# otto.net
KiCad netlist of a schematic drawn in EAGLE
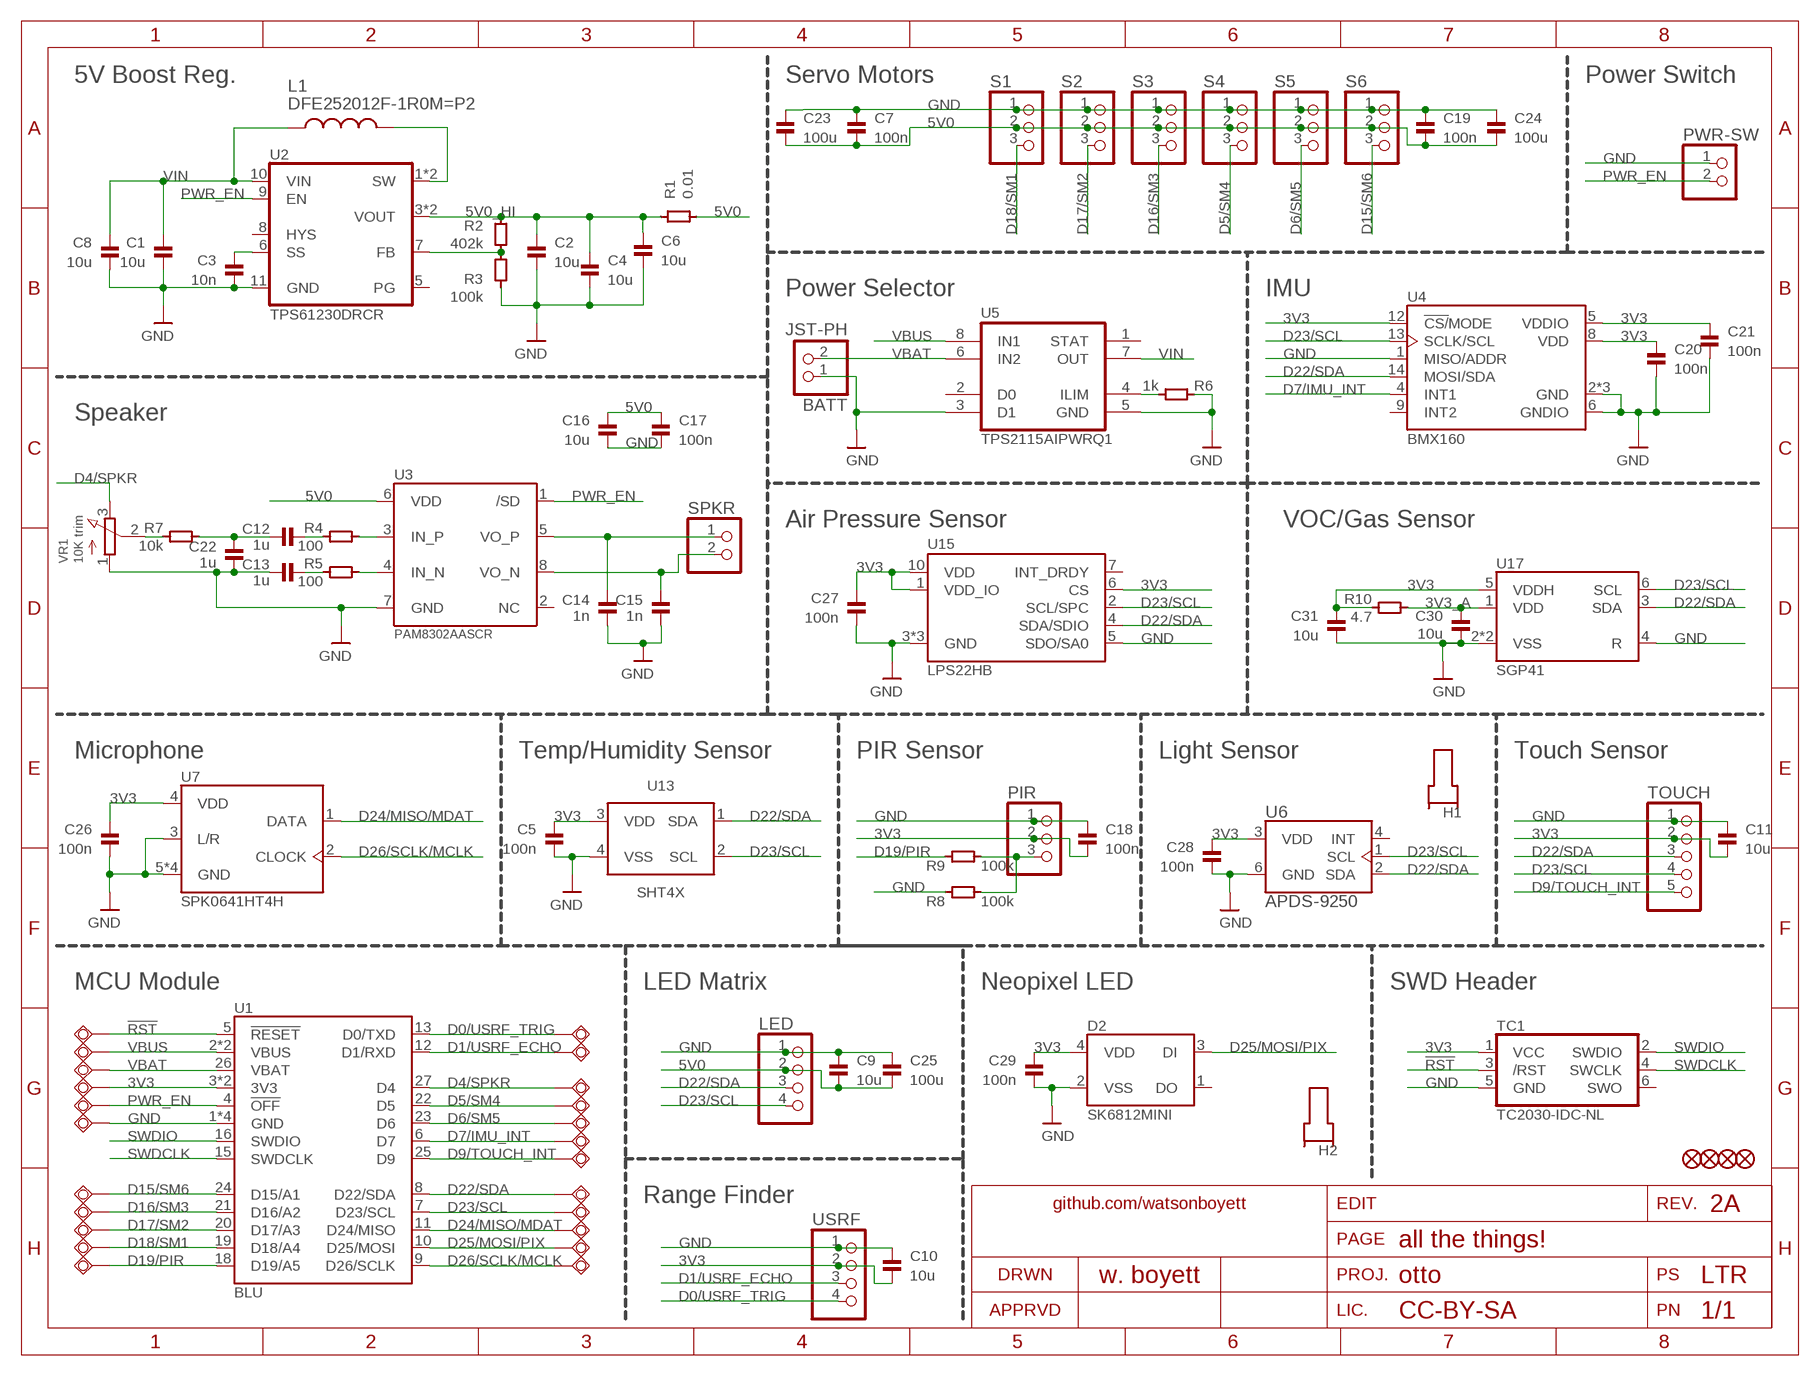
[diagram p0: schematic, sheet 1]

(export (version "E")
  (design (tool "Eeschema 10.0.6"))
  (components
    (comp (ref "3V3")
      (value "TPSQTP10R")
      (footprint "eagle-import:TP10R")
      (libsource (lib "eagle-import") (part "TPSQTP10R"))
    )
    (comp (ref "BATT")
      (value "JST-PH")
      (footprint "eagle-import:JSTPH2-S2B")
      (description "CONN HEADER SMD R/A 2POS 2MM")
      (fields
        (field (name "MFG") "JST")
        (field (name "MPN") "S2B-PH-SM4-TB(LF)(SN)")
        (field (name "PN-DGKY") "455-1749-1-ND")
      )
      (libsource (lib "eagle-import") (part "CON_JST_PH_2PIN-S2B"))
    )
    (comp (ref "C1")
      (value "10u")
      (footprint "eagle-import:_0603")
      (description "CAP CER 10UF 25V X5R 0805")
      (fields
        (field (name "MFG") "Samsung Electro-Mechanics")
        (field (name "MPN") "CL21A106KAYNNNE")
        (field (name "PN-DGKY") "445-11462-1-ND")
        (field (name "PN-DK") "1276-2891-1-ND")
      )
      (libsource (lib "eagle-import") (part "CAP_CERAMIC_0603"))
    )
    (comp (ref "C2")
      (value "10u")
      (footprint "eagle-import:_0603")
      (description "CAP CER 10UF 25V X5R 0805")
      (fields
        (field (name "MFG") "Samsung Electro-Mechanics")
        (field (name "MPN") "CL21A106KAYNNNE")
        (field (name "PN-DGKY") "445-11462-1-ND")
        (field (name "PN-DK") "1276-2891-1-ND")
      )
      (libsource (lib "eagle-import") (part "CAP_CERAMIC_0603"))
    )
    (comp (ref "C3")
      (value "10n")
      (footprint "eagle-import:_0603")
      (description "CAP CER 10UF 25V X5R 0805")
      (fields
        (field (name "MFG") "Samsung Electro-Mechanics")
        (field (name "MPN") "CL21A106KAYNNNE")
        (field (name "PN-DGKY") "445-11462-1-ND")
        (field (name "PN-DK") "1276-2891-1-ND")
      )
      (libsource (lib "eagle-import") (part "CAP_CERAMIC_0603"))
    )
    (comp (ref "C4")
      (value "10u")
      (footprint "eagle-import:_0603")
      (description "CAP CER 10UF 25V X5R 0805")
      (fields
        (field (name "MFG") "Samsung Electro-Mechanics")
        (field (name "MPN") "CL21A106KAYNNNE")
        (field (name "PN-DGKY") "445-11462-1-ND")
        (field (name "PN-DK") "1276-2891-1-ND")
      )
      (libsource (lib "eagle-import") (part "CAP_CERAMIC_0603"))
    )
    (comp (ref "C5")
      (value "100n")
      (footprint "eagle-import:_0603")
      (description "CAP CER 10UF 25V X5R 0805")
      (fields
        (field (name "MFG") "Samsung Electro-Mechanics")
        (field (name "MPN") "CL21A106KAYNNNE")
        (field (name "PN-DGKY") "445-11462-1-ND")
        (field (name "PN-DK") "1276-2891-1-ND")
      )
      (libsource (lib "eagle-import") (part "CAP_CERAMIC_0603"))
    )
    (comp (ref "C6")
      (value "10u")
      (footprint "eagle-import:_0603")
      (description "CAP CER 10UF 25V X5R 0805")
      (fields
        (field (name "MFG") "Samsung Electro-Mechanics")
        (field (name "MPN") "CL21A106KAYNNNE")
        (field (name "PN-DGKY") "445-11462-1-ND")
        (field (name "PN-DK") "1276-2891-1-ND")
      )
      (libsource (lib "eagle-import") (part "CAP_CERAMIC_0603"))
    )
    (comp (ref "C7")
      (value "100n")
      (footprint "eagle-import:_0603")
      (description "CAP CER 10UF 25V X5R 0805")
      (fields
        (field (name "MFG") "Samsung Electro-Mechanics")
        (field (name "MPN") "CL21A106KAYNNNE")
        (field (name "PN-DGKY") "445-11462-1-ND")
        (field (name "PN-DK") "1276-2891-1-ND")
      )
      (libsource (lib "eagle-import") (part "CAP_CERAMIC_0603"))
    )
    (comp (ref "C8")
      (value "10u")
      (footprint "eagle-import:_0603")
      (description "CAP CER 10UF 25V X5R 0805")
      (fields
        (field (name "MFG") "Samsung Electro-Mechanics")
        (field (name "MPN") "CL21A106KAYNNNE")
        (field (name "PN-DGKY") "445-11462-1-ND")
        (field (name "PN-DK") "1276-2891-1-ND")
      )
      (libsource (lib "eagle-import") (part "CAP_CERAMIC_0603"))
    )
    (comp (ref "C9")
      (value "10u")
      (footprint "eagle-import:_0603")
      (description "CAP CER 10UF 25V X5R 0805")
      (fields
        (field (name "MFG") "Samsung Electro-Mechanics")
        (field (name "MPN") "CL21A106KAYNNNE")
        (field (name "PN-DGKY") "445-11462-1-ND")
        (field (name "PN-DK") "1276-2891-1-ND")
      )
      (libsource (lib "eagle-import") (part "CAP_CERAMIC_0603"))
    )
    (comp (ref "C10")
      (value "10u")
      (footprint "eagle-import:_0603")
      (description "CAP CER 10UF 25V X5R 0805")
      (fields
        (field (name "MFG") "Samsung Electro-Mechanics")
        (field (name "MPN") "CL21A106KAYNNNE")
        (field (name "PN-DGKY") "445-11462-1-ND")
        (field (name "PN-DK") "1276-2891-1-ND")
      )
      (libsource (lib "eagle-import") (part "CAP_CERAMIC_0603"))
    )
    (comp (ref "C11")
      (value "10u")
      (footprint "eagle-import:_0603")
      (description "CAP CER 10UF 25V X5R 0805")
      (fields
        (field (name "MFG") "Samsung Electro-Mechanics")
        (field (name "MPN") "CL21A106KAYNNNE")
        (field (name "PN-DGKY") "445-11462-1-ND")
        (field (name "PN-DK") "1276-2891-1-ND")
      )
      (libsource (lib "eagle-import") (part "CAP_CERAMIC_0603"))
    )
    (comp (ref "C12")
      (value "1u")
      (footprint "eagle-import:_0603")
      (description "CAP CER 10UF 25V X5R 0805")
      (fields
        (field (name "MFG") "Samsung Electro-Mechanics")
        (field (name "MPN") "CL21A106KAYNNNE")
        (field (name "PN-DGKY") "445-11462-1-ND")
        (field (name "PN-DK") "1276-2891-1-ND")
      )
      (libsource (lib "eagle-import") (part "CAP_CERAMIC_0603"))
    )
    (comp (ref "C13")
      (value "1u")
      (footprint "eagle-import:_0603")
      (description "CAP CER 10UF 25V X5R 0805")
      (fields
        (field (name "MFG") "Samsung Electro-Mechanics")
        (field (name "MPN") "CL21A106KAYNNNE")
        (field (name "PN-DGKY") "445-11462-1-ND")
        (field (name "PN-DK") "1276-2891-1-ND")
      )
      (libsource (lib "eagle-import") (part "CAP_CERAMIC_0603"))
    )
    (comp (ref "C14")
      (value "1n")
      (footprint "eagle-import:_0603")
      (description "CAP CER 10UF 25V X5R 0805")
      (fields
        (field (name "MFG") "Samsung Electro-Mechanics")
        (field (name "MPN") "CL21A106KAYNNNE")
        (field (name "PN-DGKY") "445-11462-1-ND")
        (field (name "PN-DK") "1276-2891-1-ND")
      )
      (libsource (lib "eagle-import") (part "CAP_CERAMIC_0603"))
    )
    (comp (ref "C15")
      (value "1n")
      (footprint "eagle-import:_0603")
      (description "CAP CER 10UF 25V X5R 0805")
      (fields
        (field (name "MFG") "Samsung Electro-Mechanics")
        (field (name "MPN") "CL21A106KAYNNNE")
        (field (name "PN-DGKY") "445-11462-1-ND")
        (field (name "PN-DK") "1276-2891-1-ND")
      )
      (libsource (lib "eagle-import") (part "CAP_CERAMIC_0603"))
    )
    (comp (ref "C16")
      (value "10u")
      (footprint "eagle-import:_0603")
      (description "CAP CER 10UF 25V X5R 0805")
      (fields
        (field (name "MFG") "Samsung Electro-Mechanics")
        (field (name "MPN") "CL21A106KAYNNNE")
        (field (name "PN-DGKY") "445-11462-1-ND")
        (field (name "PN-DK") "1276-2891-1-ND")
      )
      (libsource (lib "eagle-import") (part "CAP_CERAMIC_0603"))
    )
    (comp (ref "C17")
      (value "100n")
      (footprint "eagle-import:_0603")
      (description "CAP CER 10UF 25V X5R 0805")
      (fields
        (field (name "MFG") "Samsung Electro-Mechanics")
        (field (name "MPN") "CL21A106KAYNNNE")
        (field (name "PN-DGKY") "445-11462-1-ND")
        (field (name "PN-DK") "1276-2891-1-ND")
      )
      (libsource (lib "eagle-import") (part "CAP_CERAMIC_0603"))
    )
    (comp (ref "C18")
      (value "100n")
      (footprint "eagle-import:_0603")
      (description "CAP CER 10UF 25V X5R 0805")
      (fields
        (field (name "MFG") "Samsung Electro-Mechanics")
        (field (name "MPN") "CL21A106KAYNNNE")
        (field (name "PN-DGKY") "445-11462-1-ND")
        (field (name "PN-DK") "1276-2891-1-ND")
      )
      (libsource (lib "eagle-import") (part "CAP_CERAMIC_0603"))
    )
    (comp (ref "C19")
      (value "100n")
      (footprint "eagle-import:_0603")
      (description "CAP CER 10UF 25V X5R 0805")
      (fields
        (field (name "MFG") "Samsung Electro-Mechanics")
        (field (name "MPN") "CL21A106KAYNNNE")
        (field (name "PN-DGKY") "445-11462-1-ND")
        (field (name "PN-DK") "1276-2891-1-ND")
      )
      (libsource (lib "eagle-import") (part "CAP_CERAMIC_0603"))
    )
    (comp (ref "C20")
      (value "100n")
      (footprint "eagle-import:_0603")
      (description "CAP CER 10UF 25V X5R 0805")
      (fields
        (field (name "MFG") "Samsung Electro-Mechanics")
        (field (name "MPN") "CL21A106KAYNNNE")
        (field (name "PN-DGKY") "445-11462-1-ND")
        (field (name "PN-DK") "1276-2891-1-ND")
      )
      (libsource (lib "eagle-import") (part "CAP_CERAMIC_0603"))
    )
    (comp (ref "C21")
      (value "100n")
      (footprint "eagle-import:_0603")
      (description "CAP CER 10UF 25V X5R 0805")
      (fields
        (field (name "MFG") "Samsung Electro-Mechanics")
        (field (name "MPN") "CL21A106KAYNNNE")
        (field (name "PN-DGKY") "445-11462-1-ND")
        (field (name "PN-DK") "1276-2891-1-ND")
      )
      (libsource (lib "eagle-import") (part "CAP_CERAMIC_0603"))
    )
    (comp (ref "C22")
      (value "1u")
      (footprint "eagle-import:_0603")
      (description "CAP CER 10UF 25V X5R 0805")
      (fields
        (field (name "MFG") "Samsung Electro-Mechanics")
        (field (name "MPN") "CL21A106KAYNNNE")
        (field (name "PN-DGKY") "445-11462-1-ND")
        (field (name "PN-DK") "1276-2891-1-ND")
      )
      (libsource (lib "eagle-import") (part "CAP_CERAMIC_0603"))
    )
    (comp (ref "C23")
      (value "100u")
      (footprint "eagle-import:_1206")
      (description "CAP CER 10UF 25V X5R 0805")
      (fields
        (field (name "MFG") "Samsung Electro-Mechanics")
        (field (name "MPN") "CL21A106KAYNNNE")
        (field (name "PN-DGKY") "445-11462-1-ND")
        (field (name "PN-DK") "1276-2891-1-ND")
      )
      (libsource (lib "eagle-import") (part "CAP_CERAMIC_1206"))
    )
    (comp (ref "C24")
      (value "100u")
      (footprint "eagle-import:_1206")
      (description "CAP CER 10UF 25V X5R 0805")
      (fields
        (field (name "MFG") "Samsung Electro-Mechanics")
        (field (name "MPN") "CL21A106KAYNNNE")
        (field (name "PN-DGKY") "445-11462-1-ND")
        (field (name "PN-DK") "1276-2891-1-ND")
      )
      (libsource (lib "eagle-import") (part "CAP_CERAMIC_1206"))
    )
    (comp (ref "C25")
      (value "100u")
      (footprint "eagle-import:_1206")
      (description "CAP CER 10UF 25V X5R 0805")
      (fields
        (field (name "MFG") "Samsung Electro-Mechanics")
        (field (name "MPN") "CL21A106KAYNNNE")
        (field (name "PN-DGKY") "445-11462-1-ND")
        (field (name "PN-DK") "1276-2891-1-ND")
      )
      (libsource (lib "eagle-import") (part "CAP_CERAMIC_1206"))
    )
    (comp (ref "C26")
      (value "100n")
      (footprint "eagle-import:_0603")
      (description "CAP CER 10UF 25V X5R 0805")
      (fields
        (field (name "MFG") "Samsung Electro-Mechanics")
        (field (name "MPN") "CL21A106KAYNNNE")
        (field (name "PN-DGKY") "445-11462-1-ND")
        (field (name "PN-DK") "1276-2891-1-ND")
      )
      (libsource (lib "eagle-import") (part "CAP_CERAMIC_0603"))
    )
    (comp (ref "C27")
      (value "100n")
      (footprint "eagle-import:_0603")
      (description "CAP CER 10UF 25V X5R 0805")
      (fields
        (field (name "MFG") "Samsung Electro-Mechanics")
        (field (name "MPN") "CL21A106KAYNNNE")
        (field (name "PN-DGKY") "445-11462-1-ND")
        (field (name "PN-DK") "1276-2891-1-ND")
      )
      (libsource (lib "eagle-import") (part "CAP_CERAMIC_0603"))
    )
    (comp (ref "C28")
      (value "100n")
      (footprint "eagle-import:_0603")
      (description "CAP CER 10UF 25V X5R 0805")
      (fields
        (field (name "MFG") "Samsung Electro-Mechanics")
        (field (name "MPN") "CL21A106KAYNNNE")
        (field (name "PN-DGKY") "445-11462-1-ND")
        (field (name "PN-DK") "1276-2891-1-ND")
      )
      (libsource (lib "eagle-import") (part "CAP_CERAMIC_0603"))
    )
    (comp (ref "C29")
      (value "100n")
      (footprint "eagle-import:_0603")
      (description "CAP CER 10UF 25V X5R 0805")
      (fields
        (field (name "MFG") "Samsung Electro-Mechanics")
        (field (name "MPN") "CL21A106KAYNNNE")
        (field (name "PN-DGKY") "445-11462-1-ND")
        (field (name "PN-DK") "1276-2891-1-ND")
      )
      (libsource (lib "eagle-import") (part "CAP_CERAMIC_0603"))
    )
    (comp (ref "C30")
      (value "10u")
      (footprint "eagle-import:_0603")
      (description "CAP CER 10UF 25V X5R 0805")
      (fields
        (field (name "MFG") "Samsung Electro-Mechanics")
        (field (name "MPN") "CL21A106KAYNNNE")
        (field (name "PN-DGKY") "445-11462-1-ND")
        (field (name "PN-DK") "1276-2891-1-ND")
      )
      (libsource (lib "eagle-import") (part "CAP_CERAMIC_0603"))
    )
    (comp (ref "C31")
      (value "10u")
      (footprint "eagle-import:_0603")
      (description "CAP CER 10UF 25V X5R 0805")
      (fields
        (field (name "MFG") "Samsung Electro-Mechanics")
        (field (name "MPN") "CL21A106KAYNNNE")
        (field (name "PN-DGKY") "445-11462-1-ND")
        (field (name "PN-DK") "1276-2891-1-ND")
      )
      (libsource (lib "eagle-import") (part "CAP_CERAMIC_0603"))
    )
    (comp (ref "D0")
      (value "TPSQTP10R")
      (footprint "eagle-import:TP10R")
      (libsource (lib "eagle-import") (part "TPSQTP10R"))
    )
    (comp (ref "D1")
      (value "TPSQTP10R")
      (footprint "eagle-import:TP10R")
      (libsource (lib "eagle-import") (part "TPSQTP10R"))
    )
    (comp (ref "D2")
      (value "SK6812MINI")
      (footprint "eagle-import:SK6812MINI")
      (fields
        (field (name "DIGI-KEY_PART_NUMBER") "1528-1542-ND")
        (field (name "MF") "Adafruit Industries")
        (field (name "MP") "2659")
      )
      (libsource (lib "eagle-import") (part "SK6812MINI"))
    )
    (comp (ref "D4")
      (value "TPSQTP10R")
      (footprint "eagle-import:TP10R")
      (libsource (lib "eagle-import") (part "TPSQTP10R"))
    )
    (comp (ref "D5")
      (value "TPSQTP10R")
      (footprint "eagle-import:TP10R")
      (libsource (lib "eagle-import") (part "TPSQTP10R"))
    )
    (comp (ref "D6")
      (value "TPSQTP10R")
      (footprint "eagle-import:TP10R")
      (libsource (lib "eagle-import") (part "TPSQTP10R"))
    )
    (comp (ref "D7")
      (value "TPSQTP10R")
      (footprint "eagle-import:TP10R")
      (libsource (lib "eagle-import") (part "TPSQTP10R"))
    )
    (comp (ref "D9")
      (value "TPSQTP10R")
      (footprint "eagle-import:TP10R")
      (libsource (lib "eagle-import") (part "TPSQTP10R"))
    )
    (comp (ref "D15")
      (value "TPSQTP10R")
      (footprint "eagle-import:TP10R")
      (libsource (lib "eagle-import") (part "TPSQTP10R"))
    )
    (comp (ref "D16")
      (value "TPSQTP10R")
      (footprint "eagle-import:TP10R")
      (libsource (lib "eagle-import") (part "TPSQTP10R"))
    )
    (comp (ref "D17")
      (value "TPSQTP10R")
      (footprint "eagle-import:TP10R")
      (libsource (lib "eagle-import") (part "TPSQTP10R"))
    )
    (comp (ref "D18")
      (value "TPSQTP10R")
      (footprint "eagle-import:TP10R")
      (libsource (lib "eagle-import") (part "TPSQTP10R"))
    )
    (comp (ref "D19")
      (value "TPSQTP10R")
      (footprint "eagle-import:TP10R")
      (libsource (lib "eagle-import") (part "TPSQTP10R"))
    )
    (comp (ref "D24")
      (value "TPSQTP10R")
      (footprint "eagle-import:TP10R")
      (libsource (lib "eagle-import") (part "TPSQTP10R"))
    )
    (comp (ref "D25")
      (value "TPSQTP10R")
      (footprint "eagle-import:TP10R")
      (libsource (lib "eagle-import") (part "TPSQTP10R"))
    )
    (comp (ref "D26")
      (value "TPSQTP10R")
      (footprint "eagle-import:TP10R")
      (libsource (lib "eagle-import") (part "TPSQTP10R"))
    )
    (comp (ref "FID1")
      (value "FIDUCIAL0.8MM")
      (footprint "eagle-import:FIDUCIAL_0.8MM")
      (libsource (lib "eagle-import") (part "FIDUCIAL0.8MM"))
    )
    (comp (ref "FID2")
      (value "FIDUCIAL0.8MM")
      (footprint "eagle-import:FIDUCIAL_0.8MM")
      (libsource (lib "eagle-import") (part "FIDUCIAL0.8MM"))
    )
    (comp (ref "FID3")
      (value "FIDUCIAL0.8MM")
      (footprint "eagle-import:FIDUCIAL_0.8MM")
      (libsource (lib "eagle-import") (part "FIDUCIAL0.8MM"))
    )
    (comp (ref "FID5")
      (value "FIDUCIAL0.8MM")
      (footprint "eagle-import:FIDUCIAL_0.8MM")
      (libsource (lib "eagle-import") (part "FIDUCIAL0.8MM"))
    )
    (comp (ref "GND")
      (value "TPSQTP10R")
      (footprint "eagle-import:TP10R")
      (libsource (lib "eagle-import") (part "TPSQTP10R"))
    )
    (comp (ref "H1")
      (value "VLP-XXX-X")
      (footprint "eagle-import:VLP-XXX-X")
      (libsource (lib "eagle-import") (part "VLP-XXX-X"))
    )
    (comp (ref "H2")
      (value "VLP-XXX-X")
      (footprint "eagle-import:VLP-XXX-X")
      (libsource (lib "eagle-import") (part "VLP-XXX-X"))
    )
    (comp (ref "L1")
      (value "DFE252012F-1R0M=P2")
      (footprint "eagle-import:INDC2520X120N")
      (fields (field (name "DIGI-KEY_PART_NUMBER") "490-13053-1-ND") (field (name "MF") "Murata Electronics"))
      (libsource (lib "eagle-import") (part "DFE252012F-1R0M=P2"))
    )
    (comp (ref "LED")
      (value "PINHD-1X4")
      (footprint "eagle-import:1X04")
      (libsource (lib "eagle-import") (part "PINHD-1X4"))
    )
    (comp (ref "PEN")
      (value "TPSQTP10R")
      (footprint "eagle-import:TP10R")
      (libsource (lib "eagle-import") (part "TPSQTP10R"))
    )
    (comp (ref "PIR")
      (value "PINHD-1X3")
      (footprint "eagle-import:1X03")
      (libsource (lib "eagle-import") (part "PINHD-1X3"))
    )
    (comp (ref "PWR-SW")
      (value "PINHD-1X2")
      (footprint "eagle-import:1X02")
      (libsource (lib "eagle-import") (part "PINHD-1X2"))
    )
    (comp (ref "R1")
      (value "0.01")
      (footprint "eagle-import:_0603")
      (libsource (lib "eagle-import") (part "RESISTOR_0603"))
    )
    (comp (ref "R2")
      (value "402k")
      (footprint "eagle-import:_0603")
      (libsource (lib "eagle-import") (part "RESISTOR_0603"))
    )
    (comp (ref "R3")
      (value "100k")
      (footprint "eagle-import:_0603")
      (libsource (lib "eagle-import") (part "RESISTOR_0603"))
    )
    (comp (ref "R4")
      (value "100")
      (footprint "eagle-import:_0603")
      (libsource (lib "eagle-import") (part "RESISTOR_0603"))
    )
    (comp (ref "R5")
      (value "100")
      (footprint "eagle-import:_0603")
      (libsource (lib "eagle-import") (part "RESISTOR_0603"))
    )
    (comp (ref "R6")
      (value "1k")
      (footprint "eagle-import:_0603")
      (libsource (lib "eagle-import") (part "RESISTOR_0603"))
    )
    (comp (ref "R7")
      (value "10k")
      (footprint "eagle-import:_0603")
      (libsource (lib "eagle-import") (part "RESISTOR_0603"))
    )
    (comp (ref "R8")
      (value "100k")
      (footprint "eagle-import:_0603")
      (libsource (lib "eagle-import") (part "RESISTOR_0603"))
    )
    (comp (ref "R9")
      (value "100k")
      (footprint "eagle-import:_0603")
      (libsource (lib "eagle-import") (part "RESISTOR_0603"))
    )
    (comp (ref "R10")
      (value "4.7")
      (footprint "eagle-import:_0603")
      (libsource (lib "eagle-import") (part "RESISTOR_0603"))
    )
    (comp (ref "RST")
      (value "TPSQTP10R")
      (footprint "eagle-import:TP10R")
      (libsource (lib "eagle-import") (part "TPSQTP10R"))
    )
    (comp (ref "S1")
      (value "PINHD-1X3")
      (footprint "eagle-import:1X03")
      (libsource (lib "eagle-import") (part "PINHD-1X3"))
    )
    (comp (ref "S2")
      (value "PINHD-1X3")
      (footprint "eagle-import:1X03")
      (libsource (lib "eagle-import") (part "PINHD-1X3"))
    )
    (comp (ref "S3")
      (value "PINHD-1X3")
      (footprint "eagle-import:1X03")
      (libsource (lib "eagle-import") (part "PINHD-1X3"))
    )
    (comp (ref "S4")
      (value "PINHD-1X3")
      (footprint "eagle-import:1X03")
      (libsource (lib "eagle-import") (part "PINHD-1X3"))
    )
    (comp (ref "S5")
      (value "PINHD-1X3")
      (footprint "eagle-import:1X03")
      (libsource (lib "eagle-import") (part "PINHD-1X3"))
    )
    (comp (ref "S6")
      (value "PINHD-1X3")
      (footprint "eagle-import:1X03")
      (libsource (lib "eagle-import") (part "PINHD-1X3"))
    )
    (comp (ref "SCL")
      (value "TPSQTP10R")
      (footprint "eagle-import:TP10R")
      (libsource (lib "eagle-import") (part "TPSQTP10R"))
    )
    (comp (ref "SDA")
      (value "TPSQTP10R")
      (footprint "eagle-import:TP10R")
      (libsource (lib "eagle-import") (part "TPSQTP10R"))
    )
    (comp (ref "SPKR")
      (value "PINHD-1X2")
      (footprint "eagle-import:1X02")
      (libsource (lib "eagle-import") (part "PINHD-1X2"))
    )
    (comp (ref "TC1")
      (value "TC2030-IDC-NL")
      (footprint "eagle-import:TC2030-NL")
      (fields (field (name "MFG") "Tag-Connect") (field (name "MPN") "TC2030-IDC"))
      (libsource (lib "eagle-import") (part "TC2030-IDC-NL"))
    )
    (comp (ref "TOUCH")
      (value "PINHD-1X5")
      (footprint "eagle-import:1X05")
      (libsource (lib "eagle-import") (part "PINHD-1X5"))
    )
    (comp (ref "U1")
      (value "BLU")
      (footprint "eagle-import:BLU")
      (libsource (lib "eagle-import") (part "BLU"))
    )
    (comp (ref "U2")
      (value "TPS61230DRCR")
      (footprint "eagle-import:VREG_V62_16624-01YE")
      (fields (field (name "DIGI-KEY_PART_NUMBER") "296-37761-1-ND") (field (name "MF") "Texas Instruments"))
      (libsource (lib "eagle-import") (part "TPS61230DRCR"))
    )
    (comp (ref "U3")
      (value "PAM8302AASCR")
      (footprint "eagle-import:MSOP8_0.65MM")
      (libsource (lib "eagle-import") (part "AUDIOAMP_PAM8302A"))
    )
    (comp (ref "U4")
      (value "BMX160")
      (footprint "eagle-import:PQFN50P250X300X100-14N")
      (fields (field (name "MF") "Bosch Sensortec"))
      (libsource (lib "eagle-import") (part "BMX160"))
    )
    (comp (ref "U5")
      (value "TPS2115AIPWRQ1")
      (footprint "eagle-import:SOP65P640X120-8N")
      (fields (field (name "MF") "Texas Instruments"))
      (libsource (lib "eagle-import") (part "TPS2115AIPWRQ1"))
    )
    (comp (ref "U6")
      (value "APDS-9250")
      (footprint "eagle-import:SON65P200X200X75-6N")
      (fields (field (name "DIGI-KEY_PART_NUMBER") "516-3293-1-ND") (field (name "MF") "Broadcom Limited"))
      (libsource (lib "eagle-import") (part "APDS-9250"))
    )
    (comp (ref "U7")
      (value "SPK0641HT4H")
      (footprint "eagle-import:SPK0641HT4H-1")
      (fields (field (name "MFG") "Knowles") (field (name "MPN") "SPK0641HT4H-1"))
      (libsource (lib "eagle-import") (part "SPK0641HT4H"))
    )
    (comp (ref "U13")
      (value "SHT4X")
      (footprint "eagle-import:SHT4X-DFN4")
      (fields (field (name "MFG") "Sensirion AG") (field (name "MPN") "SHT21"))
      (libsource (lib "eagle-import") (part "SHT4X"))
    )
    (comp (ref "U15")
      (value "LPS22HB")
      (footprint "eagle-import:HLGA-10L")
      (fields (field (name "MFG") "STMicroelectronics") (field (name "MPN") "LPS22HBTR"))
      (libsource (lib "eagle-import") (part "LPS22HB"))
    )
    (comp (ref "U17")
      (value "SGP41")
      (footprint "eagle-import:SGP41")
      (libsource (lib "eagle-import") (part "SGP41"))
    )
    (comp (ref "USRF")
      (value "PINHD-1X4")
      (footprint "eagle-import:1X04")
      (libsource (lib "eagle-import") (part "PINHD-1X4"))
    )
    (comp (ref "VBS")
      (value "TPSQTP10R")
      (footprint "eagle-import:TP10R")
      (libsource (lib "eagle-import") (part "TPSQTP10R"))
    )
    (comp (ref "VBT")
      (value "TPSQTP10R")
      (footprint "eagle-import:TP10R")
      (libsource (lib "eagle-import") (part "TPSQTP10R"))
    )
    (comp (ref "VR1")
      (value "10K trim")
      (footprint "eagle-import:TRIMPOT_BOURNS_3303W")
      (libsource (lib "eagle-import") (part "TRIMPOT3303W/X"))
    )
  )
  (nets
    (net (code "1") (name "/3V3") (class "Default")
      (node (ref "3V3") (pin "TP") (pinfunction "TP_TP") (pintype "input"))
      (node (ref "C10") (pin "2") (pinfunction "2_2") (pintype "passive"))
      (node (ref "C11") (pin "2") (pinfunction "2_2") (pintype "passive"))
      (node (ref "C18") (pin "2") (pinfunction "2_2") (pintype "passive"))
      (node (ref "C20") (pin "1") (pinfunction "1_1") (pintype "passive"))
      (node (ref "C21") (pin "1") (pinfunction "1_1") (pintype "passive"))
      (node (ref "C26") (pin "1") (pinfunction "1_1") (pintype "passive"))
      (node (ref "C27") (pin "1") (pinfunction "1_1") (pintype "passive"))
      (node (ref "C28") (pin "1") (pinfunction "1_1") (pintype "passive"))
      (node (ref "C29") (pin "1") (pinfunction "1_1") (pintype "passive"))
      (node (ref "C31") (pin "1") (pinfunction "1_1") (pintype "passive"))
      (node (ref "C5") (pin "1") (pinfunction "1_1") (pintype "passive"))
      (node (ref "D2") (pin "4") (pinfunction "VDD_4") (pintype "power_in"))
      (node (ref "PIR") (pin "2") (pinfunction "2_2") (pintype "passive"))
      (node (ref "R10") (pin "1") (pinfunction "1_1") (pintype "passive"))
      (node (ref "TC1") (pin "1") (pinfunction "VCC_1") (pintype "passive"))
      (node (ref "TOUCH") (pin "2") (pinfunction "2_2") (pintype "passive"))
      (node (ref "U1") (pin "28") (pinfunction "3V3_28") (pintype "bidirectional"))
      (node (ref "U1") (pin "3") (pinfunction "3V3_3") (pintype "bidirectional"))
      (node (ref "U13") (pin "3") (pinfunction "VDD_3") (pintype "bidirectional"))
      (node (ref "U15") (pin "1") (pinfunction "VDD_IO_1") (pintype "bidirectional"))
      (node (ref "U15") (pin "10") (pinfunction "VDD_10") (pintype "bidirectional"))
      (node (ref "U15") (pin "6") (pinfunction "CS_6") (pintype "bidirectional"))
      (node (ref "U17") (pin "5") (pinfunction "VDDH_5") (pintype "bidirectional"))
      (node (ref "U4") (pin "12") (pinfunction "~{CS/}MODE_12") (pintype "input"))
      (node (ref "U4") (pin "5") (pinfunction "VDDIO_5") (pintype "power_in"))
      (node (ref "U4") (pin "8") (pinfunction "VDD_8") (pintype "power_in"))
      (node (ref "U6") (pin "3") (pinfunction "VDD_3") (pintype "power_in"))
      (node (ref "U7") (pin "4") (pinfunction "VDD_4") (pintype "power_in"))
      (node (ref "USRF") (pin "2") (pinfunction "2_2") (pintype "passive"))
    )
    (net (code "2") (name "/3V3_A") (class "Default")
      (node (ref "C30") (pin "1") (pinfunction "1_1") (pintype "passive"))
      (node (ref "R10") (pin "2") (pinfunction "2_2") (pintype "passive"))
      (node (ref "U17") (pin "1") (pinfunction "VDD_1") (pintype "bidirectional"))
    )
    (net (code "3") (name "/5V0") (class "Default")
      (node (ref "C16") (pin "1") (pinfunction "1_1") (pintype "passive"))
      (node (ref "C17") (pin "1") (pinfunction "1_1") (pintype "passive"))
      (node (ref "C19") (pin "2") (pinfunction "2_2") (pintype "passive"))
      (node (ref "C23") (pin "2") (pinfunction "2_2") (pintype "passive"))
      (node (ref "C24") (pin "2") (pinfunction "2_2") (pintype "passive"))
      (node (ref "C25") (pin "2") (pinfunction "2_2") (pintype "passive"))
      (node (ref "C7") (pin "2") (pinfunction "2_2") (pintype "passive"))
      (node (ref "C9") (pin "2") (pinfunction "2_2") (pintype "passive"))
      (node (ref "LED") (pin "2") (pinfunction "2_2") (pintype "passive"))
      (node (ref "R1") (pin "1") (pinfunction "1_1") (pintype "passive"))
      (node (ref "S1") (pin "2") (pinfunction "2_2") (pintype "passive"))
      (node (ref "S2") (pin "2") (pinfunction "2_2") (pintype "passive"))
      (node (ref "S3") (pin "2") (pinfunction "2_2") (pintype "passive"))
      (node (ref "S4") (pin "2") (pinfunction "2_2") (pintype "passive"))
      (node (ref "S5") (pin "2") (pinfunction "2_2") (pintype "passive"))
      (node (ref "S6") (pin "2") (pinfunction "2_2") (pintype "passive"))
      (node (ref "U3") (pin "6") (pinfunction "VDD_6") (pintype "power_in"))
    )
    (net (code "4") (name "/5V0_HI") (class "Default")
      (node (ref "C2") (pin "1") (pinfunction "1_1") (pintype "passive"))
      (node (ref "C4") (pin "1") (pinfunction "1_1") (pintype "passive"))
      (node (ref "C6") (pin "1") (pinfunction "1_1") (pintype "passive"))
      (node (ref "R1") (pin "2") (pinfunction "2_2") (pintype "passive"))
      (node (ref "R2") (pin "1") (pinfunction "1_1") (pintype "passive"))
      (node (ref "U2") (pin "3") (pinfunction "VOUT_3") (pintype "output"))
      (node (ref "U2") (pin "4") (pinfunction "VOUT_4") (pintype "output"))
    )
    (net (code "5") (name "/D0{slash}USRF_TRIG") (class "Default")
      (node (ref "D0") (pin "TP") (pinfunction "TP_TP") (pintype "input"))
      (node (ref "U1") (pin "13") (pinfunction "D0/TXD_13") (pintype "bidirectional"))
      (node (ref "USRF") (pin "4") (pinfunction "4_4") (pintype "passive"))
    )
    (net (code "6") (name "/D1{slash}USRF_ECHO") (class "Default")
      (node (ref "D1") (pin "TP") (pinfunction "TP_TP") (pintype "input"))
      (node (ref "U1") (pin "12") (pinfunction "D1/RXD_12") (pintype "bidirectional"))
      (node (ref "USRF") (pin "3") (pinfunction "3_3") (pintype "passive"))
    )
    (net (code "7") (name "/D4{slash}SPKR") (class "Default")
      (node (ref "D4") (pin "TP") (pinfunction "TP_TP") (pintype "input"))
      (node (ref "U1") (pin "27") (pinfunction "D4_27") (pintype "bidirectional"))
      (node (ref "VR1") (pin "3") (pinfunction "E_3") (pintype "passive"))
    )
    (net (code "8") (name "/D5{slash}SM4") (class "Default")
      (node (ref "D5") (pin "TP") (pinfunction "TP_TP") (pintype "input"))
      (node (ref "S4") (pin "3") (pinfunction "3_3") (pintype "passive"))
      (node (ref "U1") (pin "22") (pinfunction "D5_22") (pintype "bidirectional"))
    )
    (net (code "9") (name "/D6{slash}SM5") (class "Default")
      (node (ref "D6") (pin "TP") (pinfunction "TP_TP") (pintype "input"))
      (node (ref "S5") (pin "3") (pinfunction "3_3") (pintype "passive"))
      (node (ref "U1") (pin "23") (pinfunction "D6_23") (pintype "bidirectional"))
    )
    (net (code "10") (name "/D7{slash}IMU_INT") (class "Default")
      (node (ref "D7") (pin "TP") (pinfunction "TP_TP") (pintype "input"))
      (node (ref "U1") (pin "6") (pinfunction "D7_6") (pintype "bidirectional"))
      (node (ref "U4") (pin "4") (pinfunction "INT1_4") (pintype "bidirectional"))
    )
    (net (code "11") (name "/D9{slash}TOUCH_INT") (class "Default")
      (node (ref "D9") (pin "TP") (pinfunction "TP_TP") (pintype "input"))
      (node (ref "TOUCH") (pin "5") (pinfunction "5_5") (pintype "passive"))
      (node (ref "U1") (pin "25") (pinfunction "D9_25") (pintype "bidirectional"))
    )
    (net (code "12") (name "/D15{slash}SM6") (class "Default")
      (node (ref "D15") (pin "TP") (pinfunction "TP_TP") (pintype "input"))
      (node (ref "S6") (pin "3") (pinfunction "3_3") (pintype "passive"))
      (node (ref "U1") (pin "24") (pinfunction "D15/A1_24") (pintype "bidirectional"))
    )
    (net (code "13") (name "/D16{slash}SM3") (class "Default")
      (node (ref "D16") (pin "TP") (pinfunction "TP_TP") (pintype "input"))
      (node (ref "S3") (pin "3") (pinfunction "3_3") (pintype "passive"))
      (node (ref "U1") (pin "21") (pinfunction "D16/A2_21") (pintype "bidirectional"))
    )
    (net (code "14") (name "/D17{slash}SM2") (class "Default")
      (node (ref "D17") (pin "TP") (pinfunction "TP_TP") (pintype "input"))
      (node (ref "S2") (pin "3") (pinfunction "3_3") (pintype "passive"))
      (node (ref "U1") (pin "20") (pinfunction "D17/A3_20") (pintype "bidirectional"))
    )
    (net (code "15") (name "/D18{slash}SM1") (class "Default")
      (node (ref "D18") (pin "TP") (pinfunction "TP_TP") (pintype "input"))
      (node (ref "S1") (pin "3") (pinfunction "3_3") (pintype "passive"))
      (node (ref "U1") (pin "19") (pinfunction "D18/A4_19") (pintype "bidirectional"))
    )
    (net (code "16") (name "/D19{slash}PIR") (class "Default")
      (node (ref "D19") (pin "TP") (pinfunction "TP_TP") (pintype "input"))
      (node (ref "R9") (pin "1") (pinfunction "1_1") (pintype "passive"))
      (node (ref "U1") (pin "18") (pinfunction "D19/A5_18") (pintype "bidirectional"))
    )
    (net (code "17") (name "/D22{slash}SDA") (class "Default")
      (node (ref "LED") (pin "3") (pinfunction "3_3") (pintype "passive"))
      (node (ref "SDA") (pin "TP") (pinfunction "TP_TP") (pintype "input"))
      (node (ref "TOUCH") (pin "3") (pinfunction "3_3") (pintype "passive"))
      (node (ref "U1") (pin "8") (pinfunction "D22/SDA_8") (pintype "bidirectional"))
      (node (ref "U13") (pin "1") (pinfunction "SDA_1") (pintype "bidirectional"))
      (node (ref "U15") (pin "4") (pinfunction "SDA/SDIO_4") (pintype "bidirectional"))
      (node (ref "U17") (pin "3") (pinfunction "SDA_3") (pintype "bidirectional"))
      (node (ref "U4") (pin "14") (pinfunction "MOSI/SDA_14") (pintype "bidirectional"))
      (node (ref "U6") (pin "2") (pinfunction "SDA_2") (pintype "bidirectional"))
    )
    (net (code "18") (name "/D23{slash}SCL") (class "Default")
      (node (ref "LED") (pin "4") (pinfunction "4_4") (pintype "passive"))
      (node (ref "SCL") (pin "TP") (pinfunction "TP_TP") (pintype "input"))
      (node (ref "TOUCH") (pin "4") (pinfunction "4_4") (pintype "passive"))
      (node (ref "U1") (pin "7") (pinfunction "D23/SCL_7") (pintype "bidirectional"))
      (node (ref "U13") (pin "2") (pinfunction "SCL_2") (pintype "bidirectional"))
      (node (ref "U15") (pin "2") (pinfunction "SCL/SPC_2") (pintype "bidirectional"))
      (node (ref "U17") (pin "6") (pinfunction "SCL_6") (pintype "bidirectional"))
      (node (ref "U4") (pin "13") (pinfunction "SCLK/SCL_13") (pintype "input"))
      (node (ref "U6") (pin "1") (pinfunction "SCL_1") (pintype "input"))
    )
    (net (code "19") (name "/D24{slash}MISO{slash}MDAT") (class "Default")
      (node (ref "D24") (pin "TP") (pinfunction "TP_TP") (pintype "input"))
      (node (ref "U1") (pin "11") (pinfunction "D24/MISO_11") (pintype "bidirectional"))
      (node (ref "U7") (pin "1") (pinfunction "DATA_1") (pintype "bidirectional"))
    )
    (net (code "20") (name "/D25{slash}MOSI{slash}PIX") (class "Default")
      (node (ref "D2") (pin "3") (pinfunction "DI_3") (pintype "input"))
      (node (ref "D25") (pin "TP") (pinfunction "TP_TP") (pintype "input"))
      (node (ref "U1") (pin "10") (pinfunction "D25/MOSI_10") (pintype "bidirectional"))
    )
    (net (code "21") (name "/D26{slash}SCLK{slash}MCLK") (class "Default")
      (node (ref "D26") (pin "TP") (pinfunction "TP_TP") (pintype "input"))
      (node (ref "U1") (pin "9") (pinfunction "D26/SCLK_9") (pintype "bidirectional"))
      (node (ref "U7") (pin "2") (pinfunction "CLOCK_2") (pintype "bidirectional"))
    )
    (net (code "22") (name "/PWR_EN") (class "Default")
      (node (ref "PEN") (pin "TP") (pinfunction "TP_TP") (pintype "input"))
      (node (ref "PWR-SW") (pin "2") (pinfunction "2_2") (pintype "passive"))
      (node (ref "U1") (pin "4") (pinfunction "~{OFF}_4") (pintype "bidirectional"))
      (node (ref "U2") (pin "9") (pinfunction "EN_9") (pintype "input"))
      (node (ref "U3") (pin "1") (pinfunction "/SD_1") (pintype "input"))
    )
    (net (code "23") (name "/SWDCLK") (class "Default")
      (node (ref "TC1") (pin "4") (pinfunction "SWCLK_4") (pintype "passive"))
      (node (ref "U1") (pin "15") (pinfunction "SWDCLK_15") (pintype "bidirectional"))
    )
    (net (code "24") (name "/SWDIO") (class "Default")
      (node (ref "TC1") (pin "2") (pinfunction "SWDIO_2") (pintype "passive"))
      (node (ref "U1") (pin "16") (pinfunction "SWDIO_16") (pintype "bidirectional"))
    )
    (net (code "25") (name "/VBAT") (class "Default")
      (node (ref "BATT") (pin "2") (pinfunction "2_2") (pintype "passive"))
      (node (ref "U1") (pin "26") (pinfunction "VBAT_26") (pintype "bidirectional"))
      (node (ref "U5") (pin "6") (pinfunction "IN2_6") (pintype "power_in"))
      (node (ref "VBT") (pin "TP") (pinfunction "TP_TP") (pintype "input"))
    )
    (net (code "26") (name "/VBUS") (class "Default")
      (node (ref "U1") (pin "2") (pinfunction "VBUS_2") (pintype "bidirectional"))
      (node (ref "U1") (pin "29") (pinfunction "VBUS_29") (pintype "bidirectional"))
      (node (ref "U5") (pin "8") (pinfunction "IN1_8") (pintype "power_in"))
      (node (ref "VBS") (pin "TP") (pinfunction "TP_TP") (pintype "input"))
    )
    (net (code "27") (name "/VIN") (class "Default")
      (node (ref "C1") (pin "1") (pinfunction "1_1") (pintype "passive"))
      (node (ref "C8") (pin "1") (pinfunction "1_1") (pintype "passive"))
      (node (ref "L1") (pin "1") (pinfunction "1_1") (pintype "passive"))
      (node (ref "U2") (pin "10") (pinfunction "VIN_10") (pintype "input"))
      (node (ref "U5") (pin "7") (pinfunction "OUT_7") (pintype "output"))
    )
    (net (code "28") (name "/~{RST}") (class "Default")
      (node (ref "RST") (pin "TP") (pinfunction "TP_TP") (pintype "input"))
      (node (ref "TC1") (pin "3") (pinfunction "/RST_3") (pintype "passive"))
      (node (ref "U1") (pin "5") (pinfunction "~{RESET}_5") (pintype "bidirectional"))
    )
    (net (code "29") (name "GND") (class "Default")
      (node (ref "BATT") (pin "1") (pinfunction "1_1") (pintype "passive"))
      (node (ref "C1") (pin "2") (pinfunction "2_2") (pintype "passive"))
      (node (ref "C10") (pin "1") (pinfunction "1_1") (pintype "passive"))
      (node (ref "C11") (pin "1") (pinfunction "1_1") (pintype "passive"))
      (node (ref "C13") (pin "1") (pinfunction "1_1") (pintype "passive"))
      (node (ref "C14") (pin "1") (pinfunction "1_1") (pintype "passive"))
      (node (ref "C15") (pin "1") (pinfunction "1_1") (pintype "passive"))
      (node (ref "C16") (pin "2") (pinfunction "2_2") (pintype "passive"))
      (node (ref "C17") (pin "2") (pinfunction "2_2") (pintype "passive"))
      (node (ref "C18") (pin "1") (pinfunction "1_1") (pintype "passive"))
      (node (ref "C19") (pin "1") (pinfunction "1_1") (pintype "passive"))
      (node (ref "C2") (pin "2") (pinfunction "2_2") (pintype "passive"))
      (node (ref "C20") (pin "2") (pinfunction "2_2") (pintype "passive"))
      (node (ref "C21") (pin "2") (pinfunction "2_2") (pintype "passive"))
      (node (ref "C22") (pin "1") (pinfunction "1_1") (pintype "passive"))
      (node (ref "C23") (pin "1") (pinfunction "1_1") (pintype "passive"))
      (node (ref "C24") (pin "1") (pinfunction "1_1") (pintype "passive"))
      (node (ref "C25") (pin "1") (pinfunction "1_1") (pintype "passive"))
      (node (ref "C26") (pin "2") (pinfunction "2_2") (pintype "passive"))
      (node (ref "C27") (pin "2") (pinfunction "2_2") (pintype "passive"))
      (node (ref "C28") (pin "2") (pinfunction "2_2") (pintype "passive"))
      (node (ref "C29") (pin "2") (pinfunction "2_2") (pintype "passive"))
      (node (ref "C3") (pin "2") (pinfunction "2_2") (pintype "passive"))
      (node (ref "C30") (pin "2") (pinfunction "2_2") (pintype "passive"))
      (node (ref "C31") (pin "2") (pinfunction "2_2") (pintype "passive"))
      (node (ref "C4") (pin "2") (pinfunction "2_2") (pintype "passive"))
      (node (ref "C5") (pin "2") (pinfunction "2_2") (pintype "passive"))
      (node (ref "C6") (pin "2") (pinfunction "2_2") (pintype "passive"))
      (node (ref "C7") (pin "1") (pinfunction "1_1") (pintype "passive"))
      (node (ref "C8") (pin "2") (pinfunction "2_2") (pintype "passive"))
      (node (ref "C9") (pin "1") (pinfunction "1_1") (pintype "passive"))
      (node (ref "D2") (pin "2") (pinfunction "VSS_2") (pintype "power_in"))
      (node (ref "GND") (pin "TP") (pinfunction "TP_TP") (pintype "input"))
      (node (ref "LED") (pin "1") (pinfunction "1_1") (pintype "passive"))
      (node (ref "PIR") (pin "1") (pinfunction "1_1") (pintype "passive"))
      (node (ref "PWR-SW") (pin "1") (pinfunction "1_1") (pintype "passive"))
      (node (ref "R3") (pin "2") (pinfunction "2_2") (pintype "passive"))
      (node (ref "R6") (pin "1") (pinfunction "1_1") (pintype "passive"))
      (node (ref "R8") (pin "1") (pinfunction "1_1") (pintype "passive"))
      (node (ref "S1") (pin "1") (pinfunction "1_1") (pintype "passive"))
      (node (ref "S2") (pin "1") (pinfunction "1_1") (pintype "passive"))
      (node (ref "S3") (pin "1") (pinfunction "1_1") (pintype "passive"))
      (node (ref "S4") (pin "1") (pinfunction "1_1") (pintype "passive"))
      (node (ref "S5") (pin "1") (pinfunction "1_1") (pintype "passive"))
      (node (ref "S6") (pin "1") (pinfunction "1_1") (pintype "passive"))
      (node (ref "TC1") (pin "5") (pinfunction "GND_5") (pintype "passive"))
      (node (ref "TOUCH") (pin "1") (pinfunction "1_1") (pintype "passive"))
      (node (ref "U1") (pin "1") (pinfunction "GND_1") (pintype "bidirectional"))
      (node (ref "U1") (pin "14") (pinfunction "GND_14") (pintype "bidirectional"))
      (node (ref "U1") (pin "17") (pinfunction "GND_17") (pintype "bidirectional"))
      (node (ref "U1") (pin "30") (pinfunction "GND_30") (pintype "bidirectional"))
      (node (ref "U13") (pin "4") (pinfunction "VSS_4") (pintype "bidirectional"))
      (node (ref "U15") (pin "3") (pinfunction "GND_3") (pintype "bidirectional"))
      (node (ref "U15") (pin "5") (pinfunction "SDO/SA0_5") (pintype "bidirectional"))
      (node (ref "U15") (pin "8") (pinfunction "GND_8") (pintype "bidirectional"))
      (node (ref "U15") (pin "9") (pinfunction "GND_9") (pintype "bidirectional"))
      (node (ref "U17") (pin "2") (pinfunction "VSS_2") (pintype "bidirectional"))
      (node (ref "U17") (pin "4") (pinfunction "R_4") (pintype "bidirectional"))
      (node (ref "U17") (pin "EP") (pinfunction "VSS_EP") (pintype "bidirectional"))
      (node (ref "U2") (pin "11") (pinfunction "GND_11") (pintype "power_in"))
      (node (ref "U3") (pin "7") (pinfunction "GND_7") (pintype "power_in"))
      (node (ref "U4") (pin "1") (pinfunction "MISO/ADDR_1") (pintype "bidirectional"))
      (node (ref "U4") (pin "2") (pinfunction "GND_2") (pintype "power_in"))
      (node (ref "U4") (pin "3") (pinfunction "GND_3") (pintype "power_in"))
      (node (ref "U4") (pin "6") (pinfunction "GNDIO_6") (pintype "power_in"))
      (node (ref "U4") (pin "7") (pinfunction "GND_7") (pintype "power_in"))
      (node (ref "U5") (pin "3") (pinfunction "D1_3") (pintype "input"))
      (node (ref "U5") (pin "5") (pinfunction "GND_5") (pintype "passive"))
      (node (ref "U6") (pin "6") (pinfunction "GND_6") (pintype "power_in"))
      (node (ref "U7") (pin "3") (pinfunction "L/R_3") (pintype "bidirectional"))
      (node (ref "U7") (pin "5") (pinfunction "GND_5") (pintype "power_in"))
      (node (ref "U7") (pin "6") (pinfunction "GND_6") (pintype "power_in"))
      (node (ref "U7") (pin "7") (pinfunction "GND_7") (pintype "power_in"))
      (node (ref "U7") (pin "8") (pinfunction "GND_8") (pintype "power_in"))
      (node (ref "USRF") (pin "1") (pinfunction "1_1") (pintype "passive"))
      (node (ref "VR1") (pin "1") (pinfunction "A_1") (pintype "passive"))
    )
    (net (code "30") (name "Net-(C12-Pad1)") (class "Default")
      (node (ref "C12") (pin "1") (pinfunction "1_1") (pintype "passive"))
      (node (ref "C22") (pin "2") (pinfunction "2_2") (pintype "passive"))
      (node (ref "R7") (pin "2") (pinfunction "2_2") (pintype "passive"))
    )
    (net (code "31") (name "Net-(C12-Pad2)") (class "Default")
      (node (ref "C12") (pin "2") (pinfunction "2_2") (pintype "passive"))
      (node (ref "R4") (pin "1") (pinfunction "1_1") (pintype "passive"))
    )
    (net (code "32") (name "Net-(C13-Pad2)") (class "Default")
      (node (ref "C13") (pin "2") (pinfunction "2_2") (pintype "passive"))
      (node (ref "R5") (pin "1") (pinfunction "1_1") (pintype "passive"))
    )
    (net (code "33") (name "Net-(L1-Pad2)") (class "Default")
      (node (ref "L1") (pin "2") (pinfunction "2_2") (pintype "passive"))
      (node (ref "U2") (pin "1") (pinfunction "SW_1") (pintype "output"))
      (node (ref "U2") (pin "2") (pinfunction "SW_2") (pintype "output"))
    )
    (net (code "34") (name "Net-(PIR-Pad3)") (class "Default")
      (node (ref "PIR") (pin "3") (pinfunction "3_3") (pintype "passive"))
      (node (ref "R8") (pin "2") (pinfunction "2_2") (pintype "passive"))
      (node (ref "R9") (pin "2") (pinfunction "2_2") (pintype "passive"))
    )
    (net (code "35") (name "Net-(U2-FB)") (class "Default")
      (node (ref "R2") (pin "2") (pinfunction "2_2") (pintype "passive"))
      (node (ref "R3") (pin "1") (pinfunction "1_1") (pintype "passive"))
      (node (ref "U2") (pin "7") (pinfunction "FB_7") (pintype "input"))
    )
    (net (code "36") (name "Net-(U2-SS)") (class "Default")
      (node (ref "C3") (pin "1") (pinfunction "1_1") (pintype "passive"))
      (node (ref "U2") (pin "6") (pinfunction "SS_6") (pintype "input"))
    )
    (net (code "37") (name "Net-(U3-IN_N)") (class "Default")
      (node (ref "R5") (pin "2") (pinfunction "2_2") (pintype "passive"))
      (node (ref "U3") (pin "4") (pinfunction "IN_N_4") (pintype "input"))
    )
    (net (code "38") (name "Net-(U3-IN_P)") (class "Default")
      (node (ref "R4") (pin "2") (pinfunction "2_2") (pintype "passive"))
      (node (ref "U3") (pin "3") (pinfunction "IN_P_3") (pintype "input"))
    )
    (net (code "39") (name "Net-(U3-VO_N)") (class "Default")
      (node (ref "C15") (pin "2") (pinfunction "2_2") (pintype "passive"))
      (node (ref "SPKR") (pin "2") (pinfunction "2_2") (pintype "passive"))
      (node (ref "U3") (pin "8") (pinfunction "VO_N_8") (pintype "output"))
    )
    (net (code "40") (name "Net-(U3-VO_P)") (class "Default")
      (node (ref "C14") (pin "2") (pinfunction "2_2") (pintype "passive"))
      (node (ref "SPKR") (pin "1") (pinfunction "1_1") (pintype "passive"))
      (node (ref "U3") (pin "5") (pinfunction "VO_P_5") (pintype "output"))
    )
    (net (code "41") (name "Net-(U5-ILIM)") (class "Default")
      (node (ref "R6") (pin "2") (pinfunction "2_2") (pintype "passive"))
      (node (ref "U5") (pin "4") (pinfunction "ILIM_4") (pintype "input"))
    )
    (net (code "42") (name "Net-(VR1-S)") (class "Default")
      (node (ref "R7") (pin "1") (pinfunction "1_1") (pintype "passive"))
      (node (ref "VR1") (pin "2") (pinfunction "S_2") (pintype "passive"))
    )
    (net (code "43") (name "unconnected-(D2-DO-Pad1)") (class "Default")
      (node (ref "D2") (pin "1") (pinfunction "DO_1") (pintype "output"))
    )
    (net (code "44") (name "unconnected-(TC1-SWO-Pad6)") (class "Default")
      (node (ref "TC1") (pin "6") (pinfunction "SWO_6") (pintype "passive"))
    )
    (net (code "45") (name "unconnected-(U2-HYS-Pad8)") (class "Default")
      (node (ref "U2") (pin "8") (pinfunction "HYS_8") (pintype "output"))
    )
    (net (code "46") (name "unconnected-(U2-PG-Pad5)") (class "Default")
      (node (ref "U2") (pin "5") (pinfunction "PG_5") (pintype "output"))
    )
    (net (code "47") (name "unconnected-(U3-NC-Pad2)") (class "Default")
      (node (ref "U3") (pin "2") (pinfunction "NC_2") (pintype "no_connect"))
    )
    (net (code "48") (name "unconnected-(U4-INT2-Pad9)") (class "Default")
      (node (ref "U4") (pin "9") (pinfunction "INT2_9") (pintype "bidirectional"))
    )
    (net (code "49") (name "unconnected-(U5-D0-Pad2)") (class "Default")
      (node (ref "U5") (pin "2") (pinfunction "D0_2") (pintype "input"))
    )
    (net (code "50") (name "unconnected-(U5-STAT-Pad1)") (class "Default")
      (node (ref "U5") (pin "1") (pinfunction "STAT_1") (pintype "output"))
    )
    (net (code "51") (name "unconnected-(U6-INT-Pad4)") (class "Default")
      (node (ref "U6") (pin "4") (pinfunction "INT_4") (pintype "output"))
    )
    (net (code "52") (name "unconnected-(U15-INT_DRDY-Pad7)") (class "Default")
      (node (ref "U15") (pin "7") (pinfunction "INT_DRDY_7") (pintype "bidirectional"))
    )
  )
)
